# PC4_AudioInput.net
KiCad netlist of a schematic drawn in Altium Designer
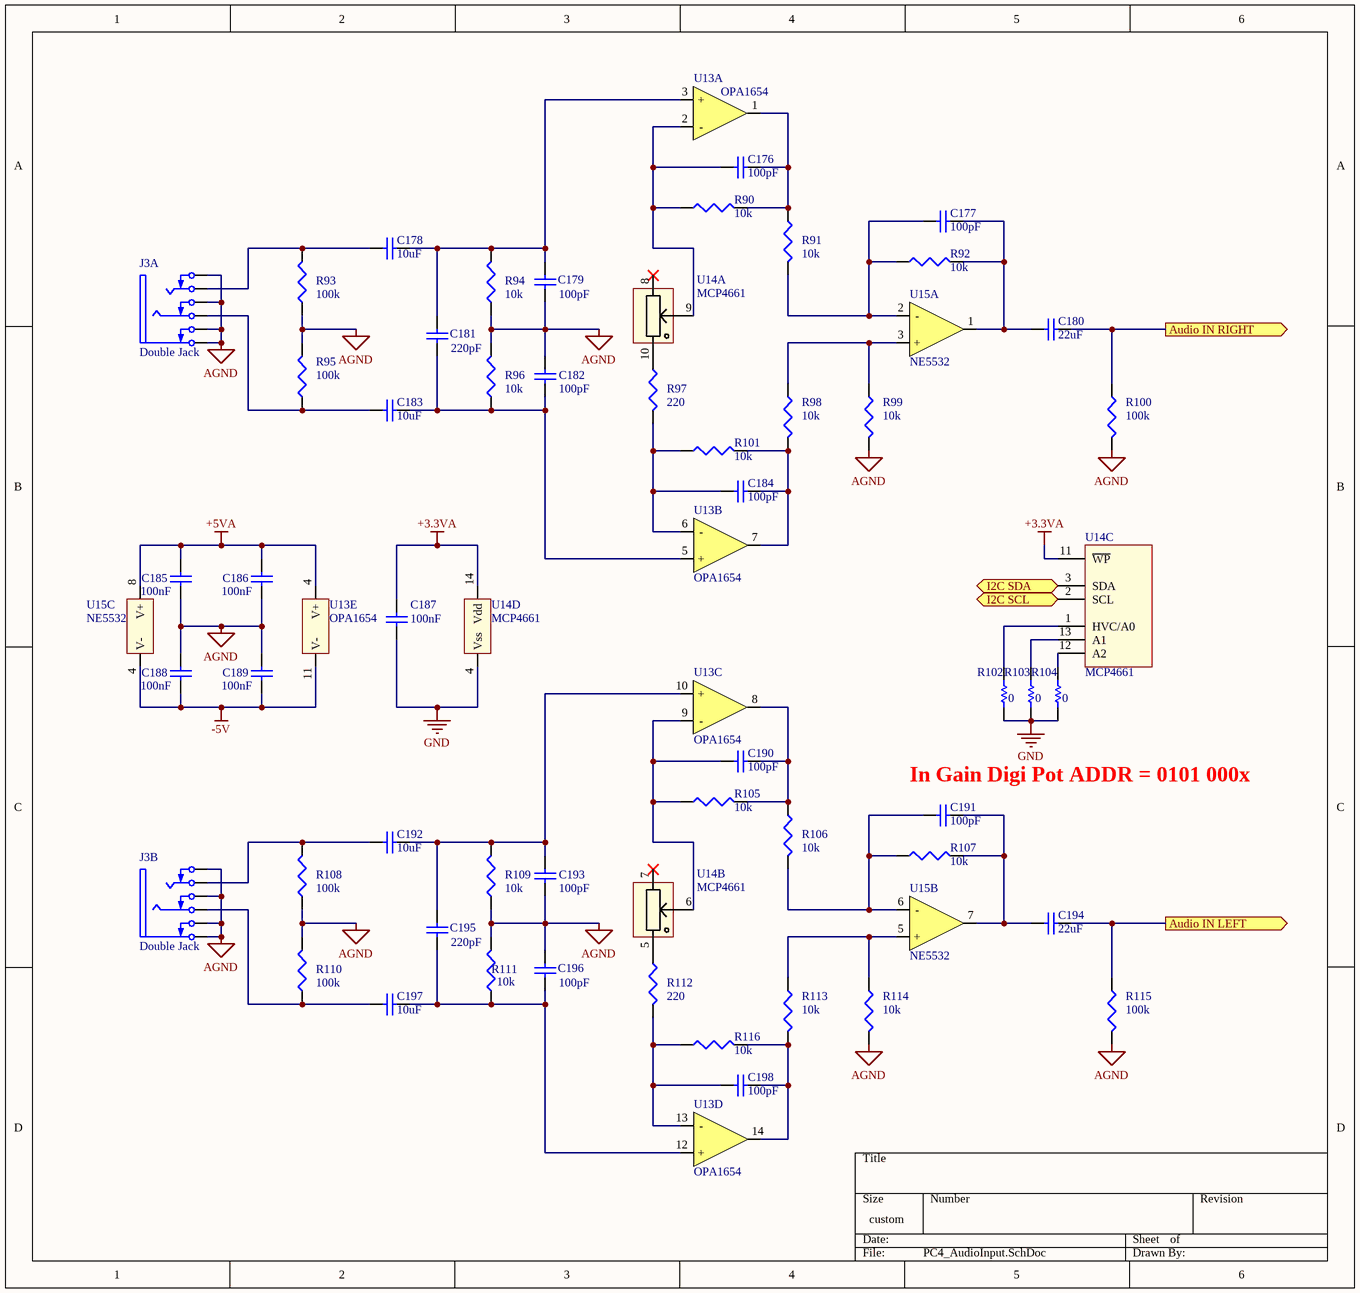
[diagram p0: PC4_AudioInput.SchDoc]

(export (version "E")
  (design (tool "Eeschema 10.0.6"))
  (components
    (comp (ref "C176")
      (value "100pF")
      (footprint "CAPC1608X08")
      (description "Capacitor")
      (fields (field (name "Comment") "Cap 100pF"))
      (libsource (lib "Michel") (part "Cap Semi"))
    )
    (comp (ref "C177")
      (value "100pF")
      (footprint "CAPC1608X08")
      (description "Capacitor")
      (fields (field (name "Comment") "Cap 100pF"))
      (libsource (lib "Michel") (part "Cap Semi"))
    )
    (comp (ref "C178")
      (value "10uF")
      (footprint "CAPC1608X08")
      (description "Capacitor")
      (fields (field (name "Comment") "Cap 10uF"))
      (libsource (lib "Michel") (part "Cap Semi"))
    )
    (comp (ref "C179")
      (value "100pF")
      (footprint "CAPC1608X08")
      (description "Capacitor")
      (fields (field (name "Comment") "Cap 100pF"))
      (libsource (lib "Michel") (part "Cap Semi"))
    )
    (comp (ref "C180")
      (value "22uF")
      (footprint "CAPC1608X08")
      (description "Capacitor")
      (fields (field (name "Comment") "Cap 22uF"))
      (libsource (lib "Michel") (part "Cap Semi"))
    )
    (comp (ref "C181")
      (value "220pF")
      (footprint "CAPC1608X08")
      (description "Capacitor")
      (fields (field (name "Comment") "Cap 220pF"))
      (libsource (lib "Michel") (part "Cap Semi"))
    )
    (comp (ref "C182")
      (value "100pF")
      (footprint "CAPC1608X08")
      (description "Capacitor")
      (fields (field (name "Comment") "Cap 100pF"))
      (libsource (lib "Michel") (part "Cap Semi"))
    )
    (comp (ref "C183")
      (value "10uF")
      (footprint "CAPC1608X08")
      (description "Capacitor")
      (fields (field (name "Comment") "Cap 10uF"))
      (libsource (lib "Michel") (part "Cap Semi"))
    )
    (comp (ref "C184")
      (value "100pF")
      (footprint "CAPC1608X08")
      (description "Capacitor")
      (fields (field (name "Comment") "Cap 100pF"))
      (libsource (lib "Michel") (part "Cap Semi"))
    )
    (comp (ref "C185")
      (value "100nF")
      (footprint "CAPC1608X08")
      (description "Capacitor")
      (fields (field (name "Comment") "Cap 100nF"))
      (libsource (lib "Michel") (part "Cap Semi"))
    )
    (comp (ref "C186")
      (value "100nF")
      (footprint "CAPC1608X08")
      (description "Capacitor")
      (fields (field (name "Comment") "Cap 100nF"))
      (libsource (lib "Michel") (part "Cap Semi"))
    )
    (comp (ref "C187")
      (value "100nF")
      (footprint "CAPC1608X08")
      (description "Capacitor")
      (fields (field (name "Comment") "Cap 100nF"))
      (libsource (lib "Michel") (part "Cap Semi"))
    )
    (comp (ref "C188")
      (value "100nF")
      (footprint "CAPC1608X08")
      (description "Capacitor")
      (fields (field (name "Comment") "Cap 100nF"))
      (libsource (lib "Michel") (part "Cap Semi"))
    )
    (comp (ref "C189")
      (value "100nF")
      (footprint "CAPC1608X08")
      (description "Capacitor")
      (fields (field (name "Comment") "Cap 100nF"))
      (libsource (lib "Michel") (part "Cap Semi"))
    )
    (comp (ref "C190")
      (value "100pF")
      (footprint "CAPC1608X08")
      (description "Capacitor")
      (fields (field (name "Comment") "Cap 100pF"))
      (libsource (lib "Michel") (part "Cap Semi"))
    )
    (comp (ref "C191")
      (value "100pF")
      (footprint "CAPC1608X08")
      (description "Capacitor")
      (fields (field (name "Comment") "Cap 100pF"))
      (libsource (lib "Michel") (part "Cap Semi"))
    )
    (comp (ref "C192")
      (value "10uF")
      (footprint "CAPC1608X08")
      (description "Capacitor")
      (fields (field (name "Comment") "Cap 10uF"))
      (libsource (lib "Michel") (part "Cap Semi"))
    )
    (comp (ref "C193")
      (value "100pF")
      (footprint "CAPC1608X08")
      (description "Capacitor")
      (fields (field (name "Comment") "Cap 100pF"))
      (libsource (lib "Michel") (part "Cap Semi"))
    )
    (comp (ref "C194")
      (value "22uF")
      (footprint "CAPC1608X08")
      (description "Capacitor")
      (fields (field (name "Comment") "Cap 22uF"))
      (libsource (lib "Michel") (part "Cap Semi"))
    )
    (comp (ref "C195")
      (value "220pF")
      (footprint "CAPC1608X08")
      (description "Capacitor")
      (fields (field (name "Comment") "Cap 220pF"))
      (libsource (lib "Michel") (part "Cap Semi"))
    )
    (comp (ref "C196")
      (value "100pF")
      (footprint "CAPC1608X08")
      (description "Capacitor")
      (fields (field (name "Comment") "Cap 100pF"))
      (libsource (lib "Michel") (part "Cap Semi"))
    )
    (comp (ref "C197")
      (value "10uF")
      (footprint "CAPC1608X08")
      (description "Capacitor")
      (fields (field (name "Comment") "Cap 10uF"))
      (libsource (lib "Michel") (part "Cap Semi"))
    )
    (comp (ref "C198")
      (value "100pF")
      (footprint "CAPC1608X08")
      (description "Capacitor")
      (fields (field (name "Comment") "Cap 100pF"))
      (libsource (lib "Michel") (part "Cap Semi"))
    )
    (comp (ref "J3")
      (value "Double Jack")
      (footprint "Amphenol_ACJS-MHDC")
      (description "Dual Jack stereo bypassed")
      (libsource (lib "Michel") (part "Dual TRS Jack Bypassed"))
    )
    (comp (ref "R90")
      (value "10k")
      (footprint "RESC1608X05")
      (description "Resistor")
      (fields (field (name "Comment") "Res 10k"))
      (libsource (lib "Michel") (part "Res3"))
    )
    (comp (ref "R91")
      (value "10k")
      (footprint "RESC1608X05")
      (description "Resistor")
      (fields (field (name "Comment") "Res 10k"))
      (libsource (lib "Michel") (part "Res3"))
    )
    (comp (ref "R92")
      (value "10k")
      (footprint "RESC1608X05")
      (description "Resistor")
      (fields (field (name "Comment") "Res 10k"))
      (libsource (lib "Michel") (part "Res3"))
    )
    (comp (ref "R93")
      (value "100k")
      (footprint "RESC1608X05")
      (description "Resistor")
      (fields (field (name "Comment") "Res 100k"))
      (libsource (lib "Michel") (part "Res3"))
    )
    (comp (ref "R94")
      (value "10k")
      (footprint "RESC1608X05")
      (description "Resistor")
      (fields (field (name "Comment") "Res 10k"))
      (libsource (lib "Michel") (part "Res3"))
    )
    (comp (ref "R95")
      (value "100k")
      (footprint "RESC1608X05")
      (description "Resistor")
      (fields (field (name "Comment") "Res 100k"))
      (libsource (lib "Michel") (part "Res3"))
    )
    (comp (ref "R96")
      (value "10k")
      (footprint "RESC1608X05")
      (description "Resistor")
      (fields (field (name "Comment") "Res 10k"))
      (libsource (lib "Michel") (part "Res3"))
    )
    (comp (ref "R97")
      (value "220")
      (footprint "RESC1608X05")
      (description "Capacitor")
      (fields (field (name "Comment") "Cap 220"))
      (libsource (lib "Michel") (part "Res3"))
    )
    (comp (ref "R98")
      (value "10k")
      (footprint "RESC1608X05")
      (description "Resistor")
      (fields (field (name "Comment") "Res 10k"))
      (libsource (lib "Michel") (part "Res3"))
    )
    (comp (ref "R99")
      (value "10k")
      (footprint "RESC1608X05")
      (description "Resistor")
      (fields (field (name "Comment") "Res 10k"))
      (libsource (lib "Michel") (part "Res3"))
    )
    (comp (ref "R100")
      (value "100k")
      (footprint "RESC1608X05")
      (description "Resistor")
      (fields (field (name "Comment") "Res 100k"))
      (libsource (lib "Michel") (part "Res3"))
    )
    (comp (ref "R101")
      (value "10k")
      (footprint "RESC1608X05")
      (description "Resistor")
      (fields (field (name "Comment") "Res 10k"))
      (libsource (lib "Michel") (part "Res3"))
    )
    (comp (ref "R102")
      (value "0")
      (footprint "RESC1608X05")
      (description "Resistor")
      (fields (field (name "Comment") "Res 0 Ohm"))
      (libsource (lib "Michel") (part "Res1"))
    )
    (comp (ref "R103")
      (value "0")
      (footprint "RESC1608X05")
      (description "Resistor")
      (fields (field (name "Comment") "Res 0 Ohm"))
      (libsource (lib "Michel") (part "Res1"))
    )
    (comp (ref "R104")
      (value "0")
      (footprint "RESC1608X05")
      (description "Resistor")
      (fields (field (name "Comment") "Res 0 Ohm"))
      (libsource (lib "Michel") (part "Res1"))
    )
    (comp (ref "R105")
      (value "10k")
      (footprint "RESC1608X05")
      (description "Resistor")
      (fields (field (name "Comment") "Res 10k"))
      (libsource (lib "Michel") (part "Res3"))
    )
    (comp (ref "R106")
      (value "10k")
      (footprint "RESC1608X05")
      (description "Resistor")
      (fields (field (name "Comment") "Res 10k"))
      (libsource (lib "Michel") (part "Res3"))
    )
    (comp (ref "R107")
      (value "10k")
      (footprint "RESC1608X05")
      (description "Resistor")
      (fields (field (name "Comment") "Res 10k"))
      (libsource (lib "Michel") (part "Res3"))
    )
    (comp (ref "R108")
      (value "100k")
      (footprint "RESC1608X05")
      (description "Resistor")
      (fields (field (name "Comment") "Res 100k"))
      (libsource (lib "Michel") (part "Res3"))
    )
    (comp (ref "R109")
      (value "10k")
      (footprint "RESC1608X05")
      (description "Resistor")
      (fields (field (name "Comment") "Res 10k"))
      (libsource (lib "Michel") (part "Res3"))
    )
    (comp (ref "R110")
      (value "100k")
      (footprint "RESC1608X05")
      (description "Resistor")
      (fields (field (name "Comment") "Res 100k"))
      (libsource (lib "Michel") (part "Res3"))
    )
    (comp (ref "R111")
      (value "10k")
      (footprint "RESC1608X05")
      (description "Resistor")
      (fields (field (name "Comment") "Res 10k"))
      (libsource (lib "Michel") (part "Res3"))
    )
    (comp (ref "R112")
      (value "220")
      (footprint "RESC1608X05")
      (description "Capacitor")
      (fields (field (name "Comment") "Cap 220"))
      (libsource (lib "Michel") (part "Res3"))
    )
    (comp (ref "R113")
      (value "10k")
      (footprint "RESC1608X05")
      (description "Resistor")
      (fields (field (name "Comment") "Res 10k"))
      (libsource (lib "Michel") (part "Res3"))
    )
    (comp (ref "R114")
      (value "10k")
      (footprint "RESC1608X05")
      (description "Resistor")
      (fields (field (name "Comment") "Res 10k"))
      (libsource (lib "Michel") (part "Res3"))
    )
    (comp (ref "R115")
      (value "100k")
      (footprint "RESC1608X05")
      (description "Resistor")
      (fields (field (name "Comment") "Res 100k"))
      (libsource (lib "Michel") (part "Res3"))
    )
    (comp (ref "R116")
      (value "10k")
      (footprint "RESC1608X05")
      (description "Resistor")
      (fields (field (name "Comment") "Res 10k"))
      (libsource (lib "Michel") (part "Res3"))
    )
    (comp (ref "U13")
      (value "OPA1654")
      (footprint "D14-M")
      (description "Quad Audio OpAmp")
      (libsource (lib "") (part "OPA1654_1"))
    )
    (comp (ref "U14")
      (value "MCP4661")
      (footprint "TSSOP14_MC-M")
      (description "Dual DigiPot non volatile I2C")
      (libsource (lib "Michel") (part "MCP4661"))
    )
    (comp (ref "U15")
      (value "NE5532")
      (footprint "D8-M")
      (description "Dual Audio OpAmp")
      (libsource (lib "Michel") (part "NE5532"))
    )
  )
  (nets
    (net (code "1") (name "+3.3VA") (class "Default")
      (node (ref "C187") (pin "1") (pinfunction "1_1") (pintype "passive"))
      (node (ref "U14") (pin "11") (pinfunction "~{WP}_11") (pintype "passive"))
      (node (ref "U14") (pin "14") (pinfunction "Vdd_14") (pintype "power_in"))
    )
    (net (code "2") (name "+5VA") (class "Default")
      (node (ref "C185") (pin "1") (pinfunction "1_1") (pintype "passive"))
      (node (ref "C186") (pin "1") (pinfunction "1_1") (pintype "passive"))
      (node (ref "U13") (pin "4") (pinfunction "V+_4") (pintype "power_in"))
      (node (ref "U15") (pin "8") (pinfunction "V+_8") (pintype "power_in"))
    )
    (net (code "3") (name "-5V") (class "Default")
      (node (ref "C188") (pin "2") (pinfunction "2_2") (pintype "passive"))
      (node (ref "C189") (pin "2") (pinfunction "2_2") (pintype "passive"))
      (node (ref "U13") (pin "11") (pinfunction "V-_11") (pintype "power_in"))
      (node (ref "U15") (pin "4") (pinfunction "V-_4") (pintype "power_in"))
    )
    (net (code "4") (name "/Audio IN LEFT") (class "Default")
      (node (ref "C194") (pin "1") (pinfunction "1_1") (pintype "passive"))
      (node (ref "R115") (pin "1") (pinfunction "1_1") (pintype "passive"))
    )
    (net (code "5") (name "/Audio IN RIGHT") (class "Default")
      (node (ref "C180") (pin "1") (pinfunction "1_1") (pintype "passive"))
      (node (ref "R100") (pin "1") (pinfunction "1_1") (pintype "passive"))
    )
    (net (code "6") (name "/I2C SCL") (class "Default")
      (node (ref "U14") (pin "2") (pinfunction "SCL_2") (pintype "passive"))
    )
    (net (code "7") (name "/I2C SDA") (class "Default")
      (node (ref "U14") (pin "3") (pinfunction "SDA_3") (pintype "passive"))
    )
    (net (code "8") (name "AGND") (class "Default")
      (node (ref "C179") (pin "2") (pinfunction "2_2") (pintype "passive"))
      (node (ref "C182") (pin "1") (pinfunction "1_1") (pintype "passive"))
      (node (ref "C185") (pin "2") (pinfunction "2_2") (pintype "passive"))
      (node (ref "C186") (pin "2") (pinfunction "2_2") (pintype "passive"))
      (node (ref "C188") (pin "1") (pinfunction "1_1") (pintype "passive"))
      (node (ref "C189") (pin "1") (pinfunction "1_1") (pintype "passive"))
      (node (ref "C193") (pin "2") (pinfunction "2_2") (pintype "passive"))
      (node (ref "C196") (pin "1") (pinfunction "1_1") (pintype "passive"))
      (node (ref "J3") (pin "1") (pinfunction "SB_1") (pintype "passive"))
      (node (ref "J3") (pin "10") (pinfunction "S_10") (pintype "power_in"))
      (node (ref "J3") (pin "2") (pinfunction "RB_2") (pintype "passive"))
      (node (ref "J3") (pin "3") (pinfunction "TB_3") (pintype "passive"))
      (node (ref "J3") (pin "4") (pinfunction "S_4") (pintype "power_in"))
      (node (ref "J3") (pin "7") (pinfunction "SB_7") (pintype "passive"))
      (node (ref "J3") (pin "8") (pinfunction "RB_8") (pintype "passive"))
      (node (ref "J3") (pin "9") (pinfunction "TB_9") (pintype "passive"))
      (node (ref "R100") (pin "2") (pinfunction "2_2") (pintype "passive"))
      (node (ref "R108") (pin "1") (pinfunction "1_1") (pintype "passive"))
      (node (ref "R109") (pin "1") (pinfunction "1_1") (pintype "passive"))
      (node (ref "R110") (pin "2") (pinfunction "2_2") (pintype "passive"))
      (node (ref "R111") (pin "2") (pinfunction "2_2") (pintype "passive"))
      (node (ref "R114") (pin "2") (pinfunction "2_2") (pintype "passive"))
      (node (ref "R115") (pin "2") (pinfunction "2_2") (pintype "passive"))
      (node (ref "R93") (pin "1") (pinfunction "1_1") (pintype "passive"))
      (node (ref "R94") (pin "1") (pinfunction "1_1") (pintype "passive"))
      (node (ref "R95") (pin "2") (pinfunction "2_2") (pintype "passive"))
      (node (ref "R96") (pin "2") (pinfunction "2_2") (pintype "passive"))
      (node (ref "R99") (pin "2") (pinfunction "2_2") (pintype "passive"))
    )
    (net (code "9") (name "GND") (class "Default")
      (node (ref "C187") (pin "2") (pinfunction "2_2") (pintype "passive"))
      (node (ref "R102") (pin "1") (pinfunction "1_1") (pintype "passive"))
      (node (ref "R103") (pin "1") (pinfunction "1_1") (pintype "passive"))
      (node (ref "R104") (pin "1") (pinfunction "1_1") (pintype "passive"))
      (node (ref "U14") (pin "4") (pinfunction "Vss_4") (pintype "power_in"))
    )
    (net (code "10") (name "Net-(J3A-R)") (class "Default")
      (node (ref "C183") (pin "2") (pinfunction "2_2") (pintype "passive"))
      (node (ref "J3") (pin "11") (pinfunction "R_11") (pintype "passive"))
      (node (ref "R95") (pin "1") (pinfunction "1_1") (pintype "passive"))
    )
    (net (code "11") (name "Net-(J3A-T)") (class "Default")
      (node (ref "C178") (pin "2") (pinfunction "2_2") (pintype "passive"))
      (node (ref "J3") (pin "12") (pinfunction "T_12") (pintype "passive"))
      (node (ref "R93") (pin "2") (pinfunction "2_2") (pintype "passive"))
    )
    (net (code "12") (name "Net-(J3B-R)") (class "Default")
      (node (ref "C197") (pin "2") (pinfunction "2_2") (pintype "passive"))
      (node (ref "J3") (pin "5") (pinfunction "R_5") (pintype "passive"))
      (node (ref "R110") (pin "1") (pinfunction "1_1") (pintype "passive"))
    )
    (net (code "13") (name "Net-(J3B-T)") (class "Default")
      (node (ref "C192") (pin "2") (pinfunction "2_2") (pintype "passive"))
      (node (ref "J3") (pin "6") (pinfunction "T_6") (pintype "passive"))
      (node (ref "R108") (pin "2") (pinfunction "2_2") (pintype "passive"))
    )
    (net (code "14") (name "Net-(U13A-+)") (class "Default")
      (node (ref "C178") (pin "1") (pinfunction "1_1") (pintype "passive"))
      (node (ref "C179") (pin "1") (pinfunction "1_1") (pintype "passive"))
      (node (ref "C181") (pin "1") (pinfunction "1_1") (pintype "passive"))
      (node (ref "R94") (pin "2") (pinfunction "2_2") (pintype "passive"))
      (node (ref "U13") (pin "3") (pinfunction "+_3") (pintype "passive"))
    )
    (net (code "15") (name "Net-(U13A--)") (class "Default")
      (node (ref "C176") (pin "1") (pinfunction "1_1") (pintype "passive"))
      (node (ref "R90") (pin "1") (pinfunction "1_1") (pintype "passive"))
      (node (ref "U13") (pin "2") (pinfunction "-_2") (pintype "passive"))
      (node (ref "U14") (pin "9") (pinfunction "P0W_9") (pintype "passive"))
    )
    (net (code "16") (name "Net-(U13A-OUT)") (class "Default")
      (node (ref "C176") (pin "2") (pinfunction "2_2") (pintype "passive"))
      (node (ref "R90") (pin "2") (pinfunction "2_2") (pintype "passive"))
      (node (ref "R91") (pin "1") (pinfunction "1_1") (pintype "passive"))
      (node (ref "U13") (pin "1") (pinfunction "OUT_1") (pintype "passive"))
    )
    (net (code "17") (name "Net-(U13B-+)") (class "Default")
      (node (ref "C181") (pin "2") (pinfunction "2_2") (pintype "passive"))
      (node (ref "C182") (pin "2") (pinfunction "2_2") (pintype "passive"))
      (node (ref "C183") (pin "1") (pinfunction "1_1") (pintype "passive"))
      (node (ref "R96") (pin "1") (pinfunction "1_1") (pintype "passive"))
      (node (ref "U13") (pin "5") (pinfunction "+_5") (pintype "passive"))
    )
    (net (code "18") (name "Net-(U13B--)") (class "Default")
      (node (ref "C184") (pin "1") (pinfunction "1_1") (pintype "passive"))
      (node (ref "R101") (pin "1") (pinfunction "1_1") (pintype "passive"))
      (node (ref "R97") (pin "2") (pinfunction "2_2") (pintype "passive"))
      (node (ref "U13") (pin "6") (pinfunction "-_6") (pintype "passive"))
    )
    (net (code "19") (name "Net-(U13B-OUT)") (class "Default")
      (node (ref "C184") (pin "2") (pinfunction "2_2") (pintype "passive"))
      (node (ref "R101") (pin "2") (pinfunction "2_2") (pintype "passive"))
      (node (ref "R98") (pin "2") (pinfunction "2_2") (pintype "passive"))
      (node (ref "U13") (pin "7") (pinfunction "OUT_7") (pintype "passive"))
    )
    (net (code "20") (name "Net-(U13C-+)") (class "Default")
      (node (ref "C192") (pin "1") (pinfunction "1_1") (pintype "passive"))
      (node (ref "C193") (pin "1") (pinfunction "1_1") (pintype "passive"))
      (node (ref "C195") (pin "1") (pinfunction "1_1") (pintype "passive"))
      (node (ref "R109") (pin "2") (pinfunction "2_2") (pintype "passive"))
      (node (ref "U13") (pin "10") (pinfunction "+_10") (pintype "passive"))
    )
    (net (code "21") (name "Net-(U13C--)") (class "Default")
      (node (ref "C190") (pin "1") (pinfunction "1_1") (pintype "passive"))
      (node (ref "R105") (pin "1") (pinfunction "1_1") (pintype "passive"))
      (node (ref "U13") (pin "9") (pinfunction "-_9") (pintype "passive"))
      (node (ref "U14") (pin "6") (pinfunction "P1W_6") (pintype "passive"))
    )
    (net (code "22") (name "Net-(U13C-OUT)") (class "Default")
      (node (ref "C190") (pin "2") (pinfunction "2_2") (pintype "passive"))
      (node (ref "R105") (pin "2") (pinfunction "2_2") (pintype "passive"))
      (node (ref "R106") (pin "1") (pinfunction "1_1") (pintype "passive"))
      (node (ref "U13") (pin "8") (pinfunction "OUT_8") (pintype "passive"))
    )
    (net (code "23") (name "Net-(U13D-+)") (class "Default")
      (node (ref "C195") (pin "2") (pinfunction "2_2") (pintype "passive"))
      (node (ref "C196") (pin "2") (pinfunction "2_2") (pintype "passive"))
      (node (ref "C197") (pin "1") (pinfunction "1_1") (pintype "passive"))
      (node (ref "R111") (pin "1") (pinfunction "1_1") (pintype "passive"))
      (node (ref "U13") (pin "12") (pinfunction "+_12") (pintype "passive"))
    )
    (net (code "24") (name "Net-(U13D--)") (class "Default")
      (node (ref "C198") (pin "1") (pinfunction "1_1") (pintype "passive"))
      (node (ref "R112") (pin "2") (pinfunction "2_2") (pintype "passive"))
      (node (ref "R116") (pin "1") (pinfunction "1_1") (pintype "passive"))
      (node (ref "U13") (pin "13") (pinfunction "-_13") (pintype "passive"))
    )
    (net (code "25") (name "Net-(U13D-OUT)") (class "Default")
      (node (ref "C198") (pin "2") (pinfunction "2_2") (pintype "passive"))
      (node (ref "R113") (pin "2") (pinfunction "2_2") (pintype "passive"))
      (node (ref "R116") (pin "2") (pinfunction "2_2") (pintype "passive"))
      (node (ref "U13") (pin "14") (pinfunction "OUT_14") (pintype "passive"))
    )
    (net (code "26") (name "Net-(U14A-P0B)") (class "Default")
      (node (ref "R97") (pin "1") (pinfunction "1_1") (pintype "passive"))
      (node (ref "U14") (pin "10") (pinfunction "P0B_10") (pintype "passive"))
    )
    (net (code "27") (name "Net-(U14B-P1B)") (class "Default")
      (node (ref "R112") (pin "1") (pinfunction "1_1") (pintype "passive"))
      (node (ref "U14") (pin "5") (pinfunction "P1B_5") (pintype "passive"))
    )
    (net (code "28") (name "Net-(U14C-A1)") (class "Default")
      (node (ref "R103") (pin "2") (pinfunction "2_2") (pintype "passive"))
      (node (ref "U14") (pin "13") (pinfunction "A1_13") (pintype "power_in"))
    )
    (net (code "29") (name "Net-(U14C-A2)") (class "Default")
      (node (ref "R104") (pin "2") (pinfunction "2_2") (pintype "passive"))
      (node (ref "U14") (pin "12") (pinfunction "A2_12") (pintype "power_in"))
    )
    (net (code "30") (name "Net-(U14C-HVC{slash}A0)") (class "Default")
      (node (ref "R102") (pin "2") (pinfunction "2_2") (pintype "passive"))
      (node (ref "U14") (pin "1") (pinfunction "HVC/A0_1") (pintype "power_in"))
    )
    (net (code "31") (name "Net-(U15A-+)") (class "Default")
      (node (ref "R98") (pin "1") (pinfunction "1_1") (pintype "passive"))
      (node (ref "R99") (pin "1") (pinfunction "1_1") (pintype "passive"))
      (node (ref "U15") (pin "3") (pinfunction "+_3") (pintype "passive"))
    )
    (net (code "32") (name "Net-(U15A--)") (class "Default")
      (node (ref "C177") (pin "1") (pinfunction "1_1") (pintype "passive"))
      (node (ref "R91") (pin "2") (pinfunction "2_2") (pintype "passive"))
      (node (ref "R92") (pin "1") (pinfunction "1_1") (pintype "passive"))
      (node (ref "U15") (pin "2") (pinfunction "-_2") (pintype "passive"))
    )
    (net (code "33") (name "Net-(U15A-OUT)") (class "Default")
      (node (ref "C177") (pin "2") (pinfunction "2_2") (pintype "passive"))
      (node (ref "C180") (pin "2") (pinfunction "2_2") (pintype "passive"))
      (node (ref "R92") (pin "2") (pinfunction "2_2") (pintype "passive"))
      (node (ref "U15") (pin "1") (pinfunction "OUT_1") (pintype "passive"))
    )
    (net (code "34") (name "Net-(U15B-+)") (class "Default")
      (node (ref "R113") (pin "1") (pinfunction "1_1") (pintype "passive"))
      (node (ref "R114") (pin "1") (pinfunction "1_1") (pintype "passive"))
      (node (ref "U15") (pin "5") (pinfunction "+_5") (pintype "passive"))
    )
    (net (code "35") (name "Net-(U15B--)") (class "Default")
      (node (ref "C191") (pin "1") (pinfunction "1_1") (pintype "passive"))
      (node (ref "R106") (pin "2") (pinfunction "2_2") (pintype "passive"))
      (node (ref "R107") (pin "1") (pinfunction "1_1") (pintype "passive"))
      (node (ref "U15") (pin "6") (pinfunction "-_6") (pintype "passive"))
    )
    (net (code "36") (name "Net-(U15B-OUT)") (class "Default")
      (node (ref "C191") (pin "2") (pinfunction "2_2") (pintype "passive"))
      (node (ref "C194") (pin "2") (pinfunction "2_2") (pintype "passive"))
      (node (ref "R107") (pin "2") (pinfunction "2_2") (pintype "passive"))
      (node (ref "U15") (pin "7") (pinfunction "OUT_7") (pintype "passive"))
    )
    (net (code "37") (name "unconnected-(U14A-P0A-Pad8)") (class "Default")
      (node (ref "U14") (pin "8") (pinfunction "P0A_8") (pintype "passive+no_connect"))
    )
    (net (code "38") (name "unconnected-(U14B-P1A-Pad7)") (class "Default")
      (node (ref "U14") (pin "7") (pinfunction "P1A_7") (pintype "passive+no_connect"))
    )
  )
)
